# fpga-bank6-inside.net
KiCad netlist of a schematic drawn in Altium Designer
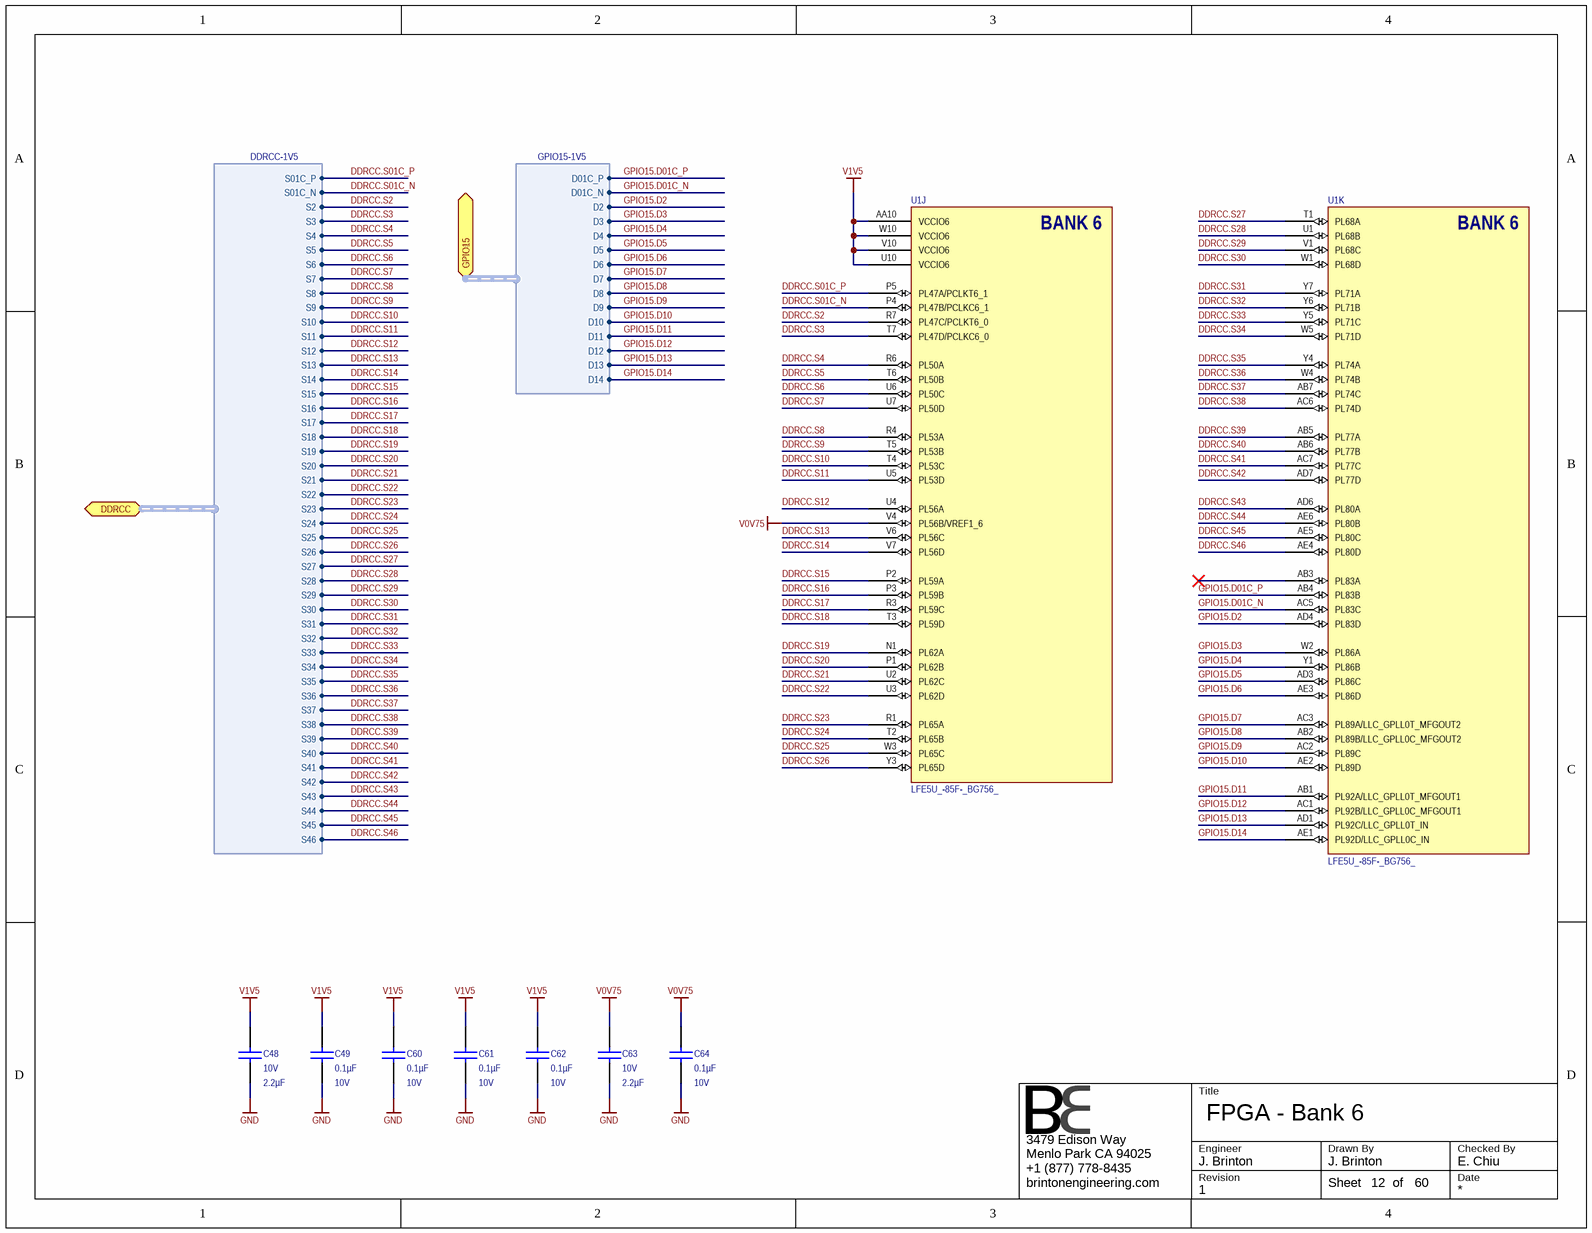
[diagram p0: fpga-bank6-inside.SchDoc]

(export (version "E")
  (design (tool "Eeschema 10.0.6"))
  (components
    (comp (ref "C48")
      (value "GRM188R71A225KE15D")
      (footprint "CAPC1608X90N")
      (description "CAP CER 2.2UF 10V 10% X7R 0603")
      (fields
        (field (name "MANUFACTURER") "Murata Electronics North America")
        (field (name "TOLERANCE") "±10%")
        (field (name "VOLTAGE - RATED") "10V")
        (field (name "CAPACITANCE") "2.2µF")
      )
      (libsource (lib "murata") (part "GRM188R71A225KE15D"))
    )
    (comp (ref "C49")
      (value "GRM155R71A104KA01J")
      (footprint "CAPC1005X56N")
      (description "CAP CER 0.1UF 10V 10% X7R 0402")
      (fields
        (field (name "MANUFACTURER") "Murata Electronics North America")
        (field (name "TOLERANCE") "±10%")
        (field (name "CAPACITANCE") "0.1µF")
        (field (name "VOLTAGE - RATED") "10V")
      )
      (libsource (lib "murata") (part "GRM155R71A104KA01J"))
    )
    (comp (ref "C60")
      (value "GRM155R71A104KA01J")
      (footprint "CAPC1005X56N")
      (description "CAP CER 0.1UF 10V 10% X7R 0402")
      (fields
        (field (name "MANUFACTURER") "Murata Electronics North America")
        (field (name "TOLERANCE") "±10%")
        (field (name "CAPACITANCE") "0.1µF")
        (field (name "VOLTAGE - RATED") "10V")
      )
      (libsource (lib "murata") (part "GRM155R71A104KA01J"))
    )
    (comp (ref "C61")
      (value "GRM155R71A104KA01J")
      (footprint "CAPC1005X56N")
      (description "CAP CER 0.1UF 10V 10% X7R 0402")
      (fields
        (field (name "MANUFACTURER") "Murata Electronics North America")
        (field (name "TOLERANCE") "±10%")
        (field (name "CAPACITANCE") "0.1µF")
        (field (name "VOLTAGE - RATED") "10V")
      )
      (libsource (lib "murata") (part "GRM155R71A104KA01J"))
    )
    (comp (ref "C62")
      (value "GRM155R71A104KA01J")
      (footprint "CAPC1005X56N")
      (description "CAP CER 0.1UF 10V 10% X7R 0402")
      (fields
        (field (name "MANUFACTURER") "Murata Electronics North America")
        (field (name "TOLERANCE") "±10%")
        (field (name "CAPACITANCE") "0.1µF")
        (field (name "VOLTAGE - RATED") "10V")
      )
      (libsource (lib "murata") (part "GRM155R71A104KA01J"))
    )
    (comp (ref "C63")
      (value "GRM188R71A225KE15D")
      (footprint "CAPC1608X90N")
      (description "CAP CER 2.2UF 10V 10% X7R 0603")
      (fields
        (field (name "MANUFACTURER") "Murata Electronics North America")
        (field (name "TOLERANCE") "±10%")
        (field (name "VOLTAGE - RATED") "10V")
        (field (name "CAPACITANCE") "2.2µF")
      )
      (libsource (lib "murata") (part "GRM188R71A225KE15D"))
    )
    (comp (ref "C64")
      (value "GRM155R71A104KA01J")
      (footprint "CAPC1005X56N")
      (description "CAP CER 0.1UF 10V 10% X7R 0402")
      (fields
        (field (name "MANUFACTURER") "Murata Electronics North America")
        (field (name "TOLERANCE") "±10%")
        (field (name "CAPACITANCE") "0.1µF")
        (field (name "VOLTAGE - RATED") "10V")
      )
      (libsource (lib "murata") (part "GRM155R71A104KA01J"))
    )
    (comp (ref "U1")
      (value "LFE5U_-85F-_BG756_")
      (footprint "lattice:caBGA756")
      (description "ECP5 FPGA, 85k LUT, 756-caBGA")
      (fields (field (name "MANUFACTURER") "Lattice Semiconductor"))
      (libsource (lib "lattice") (part "LFE5U_-85F-_BG756_"))
    )
  )
  (nets
    (net (code "3") (name "/DDRCC.S01C_N") (class "Default")
      (node (ref "U1") (pin "P4") (pinfunction "PL47B/PCLKC6_1_P4") (pintype "bidirectional"))
    )
    (net (code "4") (name "/DDRCC.S01C_P") (class "Default")
      (node (ref "U1") (pin "P5") (pinfunction "PL47A/PCLKT6_1_P5") (pintype "bidirectional"))
    )
    (net (code "5") (name "/DDRCC.S2") (class "Default")
      (node (ref "U1") (pin "R7") (pinfunction "PL47C/PCLKT6_0_R7") (pintype "bidirectional"))
    )
    (net (code "6") (name "/DDRCC.S3") (class "Default")
      (node (ref "U1") (pin "T7") (pinfunction "PL47D/PCLKC6_0_T7") (pintype "bidirectional"))
    )
    (net (code "7") (name "/DDRCC.S4") (class "Default")
      (node (ref "U1") (pin "R6") (pinfunction "PL50A_R6") (pintype "bidirectional"))
    )
    (net (code "8") (name "/DDRCC.S5") (class "Default")
      (node (ref "U1") (pin "T6") (pinfunction "PL50B_T6") (pintype "bidirectional"))
    )
    (net (code "9") (name "/DDRCC.S6") (class "Default")
      (node (ref "U1") (pin "U6") (pinfunction "PL50C_U6") (pintype "bidirectional"))
    )
    (net (code "10") (name "/DDRCC.S7") (class "Default")
      (node (ref "U1") (pin "U7") (pinfunction "PL50D_U7") (pintype "bidirectional"))
    )
    (net (code "11") (name "/DDRCC.S8") (class "Default")
      (node (ref "U1") (pin "R4") (pinfunction "PL53A_R4") (pintype "bidirectional"))
    )
    (net (code "12") (name "/DDRCC.S9") (class "Default")
      (node (ref "U1") (pin "T5") (pinfunction "PL53B_T5") (pintype "bidirectional"))
    )
    (net (code "13") (name "/DDRCC.S10") (class "Default")
      (node (ref "U1") (pin "T4") (pinfunction "PL53C_T4") (pintype "bidirectional"))
    )
    (net (code "14") (name "/DDRCC.S11") (class "Default")
      (node (ref "U1") (pin "U5") (pinfunction "PL53D_U5") (pintype "bidirectional"))
    )
    (net (code "15") (name "/DDRCC.S12") (class "Default")
      (node (ref "U1") (pin "U4") (pinfunction "PL56A_U4") (pintype "bidirectional"))
    )
    (net (code "16") (name "/DDRCC.S13") (class "Default")
      (node (ref "U1") (pin "V6") (pinfunction "PL56C_V6") (pintype "bidirectional"))
    )
    (net (code "17") (name "/DDRCC.S14") (class "Default")
      (node (ref "U1") (pin "V7") (pinfunction "PL56D_V7") (pintype "bidirectional"))
    )
    (net (code "18") (name "/DDRCC.S15") (class "Default")
      (node (ref "U1") (pin "P2") (pinfunction "PL59A_P2") (pintype "bidirectional"))
    )
    (net (code "19") (name "/DDRCC.S16") (class "Default")
      (node (ref "U1") (pin "P3") (pinfunction "PL59B_P3") (pintype "bidirectional"))
    )
    (net (code "20") (name "/DDRCC.S17") (class "Default")
      (node (ref "U1") (pin "R3") (pinfunction "PL59C_R3") (pintype "bidirectional"))
    )
    (net (code "21") (name "/DDRCC.S18") (class "Default")
      (node (ref "U1") (pin "T3") (pinfunction "PL59D_T3") (pintype "bidirectional"))
    )
    (net (code "22") (name "/DDRCC.S19") (class "Default")
      (node (ref "U1") (pin "N1") (pinfunction "PL62A_N1") (pintype "bidirectional"))
    )
    (net (code "23") (name "/DDRCC.S20") (class "Default")
      (node (ref "U1") (pin "P1") (pinfunction "PL62B_P1") (pintype "bidirectional"))
    )
    (net (code "24") (name "/DDRCC.S21") (class "Default")
      (node (ref "U1") (pin "U2") (pinfunction "PL62C_U2") (pintype "bidirectional"))
    )
    (net (code "25") (name "/DDRCC.S22") (class "Default")
      (node (ref "U1") (pin "U3") (pinfunction "PL62D_U3") (pintype "bidirectional"))
    )
    (net (code "26") (name "/DDRCC.S23") (class "Default")
      (node (ref "U1") (pin "R1") (pinfunction "PL65A_R1") (pintype "bidirectional"))
    )
    (net (code "27") (name "/DDRCC.S24") (class "Default")
      (node (ref "U1") (pin "T2") (pinfunction "PL65B_T2") (pintype "bidirectional"))
    )
    (net (code "28") (name "/DDRCC.S25") (class "Default")
      (node (ref "U1") (pin "W3") (pinfunction "PL65C_W3") (pintype "bidirectional"))
    )
    (net (code "29") (name "/DDRCC.S26") (class "Default")
      (node (ref "U1") (pin "Y3") (pinfunction "PL65D_Y3") (pintype "bidirectional"))
    )
    (net (code "30") (name "/DDRCC.S27") (class "Default")
      (node (ref "U1") (pin "T1") (pinfunction "PL68A_T1") (pintype "bidirectional"))
    )
    (net (code "31") (name "/DDRCC.S28") (class "Default")
      (node (ref "U1") (pin "U1") (pinfunction "PL68B_U1") (pintype "bidirectional"))
    )
    (net (code "32") (name "/DDRCC.S29") (class "Default")
      (node (ref "U1") (pin "V1") (pinfunction "PL68C_V1") (pintype "bidirectional"))
    )
    (net (code "33") (name "/DDRCC.S30") (class "Default")
      (node (ref "U1") (pin "W1") (pinfunction "PL68D_W1") (pintype "bidirectional"))
    )
    (net (code "34") (name "/DDRCC.S31") (class "Default")
      (node (ref "U1") (pin "Y7") (pinfunction "PL71A_Y7") (pintype "bidirectional"))
    )
    (net (code "35") (name "/DDRCC.S32") (class "Default")
      (node (ref "U1") (pin "Y6") (pinfunction "PL71B_Y6") (pintype "bidirectional"))
    )
    (net (code "36") (name "/DDRCC.S33") (class "Default")
      (node (ref "U1") (pin "Y5") (pinfunction "PL71C_Y5") (pintype "bidirectional"))
    )
    (net (code "37") (name "/DDRCC.S34") (class "Default")
      (node (ref "U1") (pin "W5") (pinfunction "PL71D_W5") (pintype "bidirectional"))
    )
    (net (code "38") (name "/DDRCC.S35") (class "Default")
      (node (ref "U1") (pin "Y4") (pinfunction "PL74A_Y4") (pintype "bidirectional"))
    )
    (net (code "39") (name "/DDRCC.S36") (class "Default")
      (node (ref "U1") (pin "W4") (pinfunction "PL74B_W4") (pintype "bidirectional"))
    )
    (net (code "40") (name "/DDRCC.S37") (class "Default")
      (node (ref "U1") (pin "AB7") (pinfunction "PL74C_AB7") (pintype "bidirectional"))
    )
    (net (code "41") (name "/DDRCC.S38") (class "Default")
      (node (ref "U1") (pin "AC6") (pinfunction "PL74D_AC6") (pintype "bidirectional"))
    )
    (net (code "42") (name "/DDRCC.S39") (class "Default")
      (node (ref "U1") (pin "AB5") (pinfunction "PL77A_AB5") (pintype "bidirectional"))
    )
    (net (code "43") (name "/DDRCC.S40") (class "Default")
      (node (ref "U1") (pin "AB6") (pinfunction "PL77B_AB6") (pintype "bidirectional"))
    )
    (net (code "44") (name "/DDRCC.S41") (class "Default")
      (node (ref "U1") (pin "AC7") (pinfunction "PL77C_AC7") (pintype "bidirectional"))
    )
    (net (code "45") (name "/DDRCC.S42") (class "Default")
      (node (ref "U1") (pin "AD7") (pinfunction "PL77D_AD7") (pintype "bidirectional"))
    )
    (net (code "46") (name "/DDRCC.S43") (class "Default")
      (node (ref "U1") (pin "AD6") (pinfunction "PL80A_AD6") (pintype "bidirectional"))
    )
    (net (code "47") (name "/DDRCC.S44") (class "Default")
      (node (ref "U1") (pin "AE6") (pinfunction "PL80B_AE6") (pintype "bidirectional"))
    )
    (net (code "48") (name "/DDRCC.S45") (class "Default")
      (node (ref "U1") (pin "AE5") (pinfunction "PL80C_AE5") (pintype "bidirectional"))
    )
    (net (code "49") (name "/DDRCC.S46") (class "Default")
      (node (ref "U1") (pin "AE4") (pinfunction "PL80D_AE4") (pintype "bidirectional"))
    )
    (net (code "50") (name "/GPIO15.D01C_N") (class "Default")
      (node (ref "U1") (pin "AC5") (pinfunction "PL83C_AC5") (pintype "bidirectional"))
    )
    (net (code "51") (name "/GPIO15.D01C_P") (class "Default")
      (node (ref "U1") (pin "AB4") (pinfunction "PL83B_AB4") (pintype "bidirectional"))
    )
    (net (code "52") (name "/GPIO15.D2") (class "Default")
      (node (ref "U1") (pin "AD4") (pinfunction "PL83D_AD4") (pintype "bidirectional"))
    )
    (net (code "53") (name "/GPIO15.D3") (class "Default")
      (node (ref "U1") (pin "W2") (pinfunction "PL86A_W2") (pintype "bidirectional"))
    )
    (net (code "54") (name "/GPIO15.D4") (class "Default")
      (node (ref "U1") (pin "Y1") (pinfunction "PL86B_Y1") (pintype "bidirectional"))
    )
    (net (code "55") (name "/GPIO15.D5") (class "Default")
      (node (ref "U1") (pin "AD3") (pinfunction "PL86C_AD3") (pintype "bidirectional"))
    )
    (net (code "56") (name "/GPIO15.D6") (class "Default")
      (node (ref "U1") (pin "AE3") (pinfunction "PL86D_AE3") (pintype "bidirectional"))
    )
    (net (code "57") (name "/GPIO15.D7") (class "Default")
      (node (ref "U1") (pin "AC3") (pinfunction "PL89A/LLC_GPLL0T_MFGOUT2_AC3") (pintype "bidirectional"))
    )
    (net (code "58") (name "/GPIO15.D8") (class "Default")
      (node (ref "U1") (pin "AB2") (pinfunction "PL89B/LLC_GPLL0C_MFGOUT2_AB2") (pintype "bidirectional"))
    )
    (net (code "59") (name "/GPIO15.D9") (class "Default")
      (node (ref "U1") (pin "AC2") (pinfunction "PL89C_AC2") (pintype "bidirectional"))
    )
    (net (code "60") (name "/GPIO15.D10") (class "Default")
      (node (ref "U1") (pin "AE2") (pinfunction "PL89D_AE2") (pintype "bidirectional"))
    )
    (net (code "61") (name "/GPIO15.D11") (class "Default")
      (node (ref "U1") (pin "AB1") (pinfunction "PL92A/LLC_GPLL0T_MFGOUT1_AB1") (pintype "bidirectional"))
    )
    (net (code "62") (name "/GPIO15.D12") (class "Default")
      (node (ref "U1") (pin "AC1") (pinfunction "PL92B/LLC_GPLL0C_MFGOUT1_AC1") (pintype "bidirectional"))
    )
    (net (code "63") (name "/GPIO15.D13") (class "Default")
      (node (ref "U1") (pin "AD1") (pinfunction "PL92C/LLC_GPLL0T_IN_AD1") (pintype "bidirectional"))
    )
    (net (code "64") (name "/GPIO15.D14") (class "Default")
      (node (ref "U1") (pin "AE1") (pinfunction "PL92D/LLC_GPLL0C_IN_AE1") (pintype "bidirectional"))
    )
    (net (code "67") (name "GND") (class "Default")
      (node (ref "C48") (pin "1") (pinfunction "1_1") (pintype "passive"))
      (node (ref "C49") (pin "1") (pinfunction "1_1") (pintype "passive"))
      (node (ref "C60") (pin "1") (pinfunction "1_1") (pintype "passive"))
      (node (ref "C61") (pin "1") (pinfunction "1_1") (pintype "passive"))
      (node (ref "C62") (pin "1") (pinfunction "1_1") (pintype "passive"))
      (node (ref "C63") (pin "1") (pinfunction "1_1") (pintype "passive"))
      (node (ref "C64") (pin "1") (pinfunction "1_1") (pintype "passive"))
    )
    (net (code "68") (name "V0V75") (class "Default")
      (node (ref "C63") (pin "2") (pinfunction "2_2") (pintype "passive"))
      (node (ref "C64") (pin "2") (pinfunction "2_2") (pintype "passive"))
      (node (ref "U1") (pin "V4") (pinfunction "PL56B/VREF1_6_V4") (pintype "bidirectional"))
    )
    (net (code "69") (name "V1V5") (class "Default")
      (node (ref "C48") (pin "2") (pinfunction "2_2") (pintype "passive"))
      (node (ref "C49") (pin "2") (pinfunction "2_2") (pintype "passive"))
      (node (ref "C60") (pin "2") (pinfunction "2_2") (pintype "passive"))
      (node (ref "C61") (pin "2") (pinfunction "2_2") (pintype "passive"))
      (node (ref "C62") (pin "2") (pinfunction "2_2") (pintype "passive"))
      (node (ref "U1") (pin "AA10") (pinfunction "VCCIO6_AA10") (pintype "power_in"))
      (node (ref "U1") (pin "U10") (pinfunction "VCCIO6_U10") (pintype "power_in"))
      (node (ref "U1") (pin "V10") (pinfunction "VCCIO6_V10") (pintype "power_in"))
      (node (ref "U1") (pin "W10") (pinfunction "VCCIO6_W10") (pintype "power_in"))
    )
    (net (code "70") (name "unconnected-(U1K-PL83A-PadAB3)") (class "Default")
      (node (ref "U1") (pin "AB3") (pinfunction "PL83A_AB3") (pintype "bidirectional+no_connect"))
    )
  )
)
